# dub_synth.net
KiCad netlist of a schematic drawn in Altium Designer
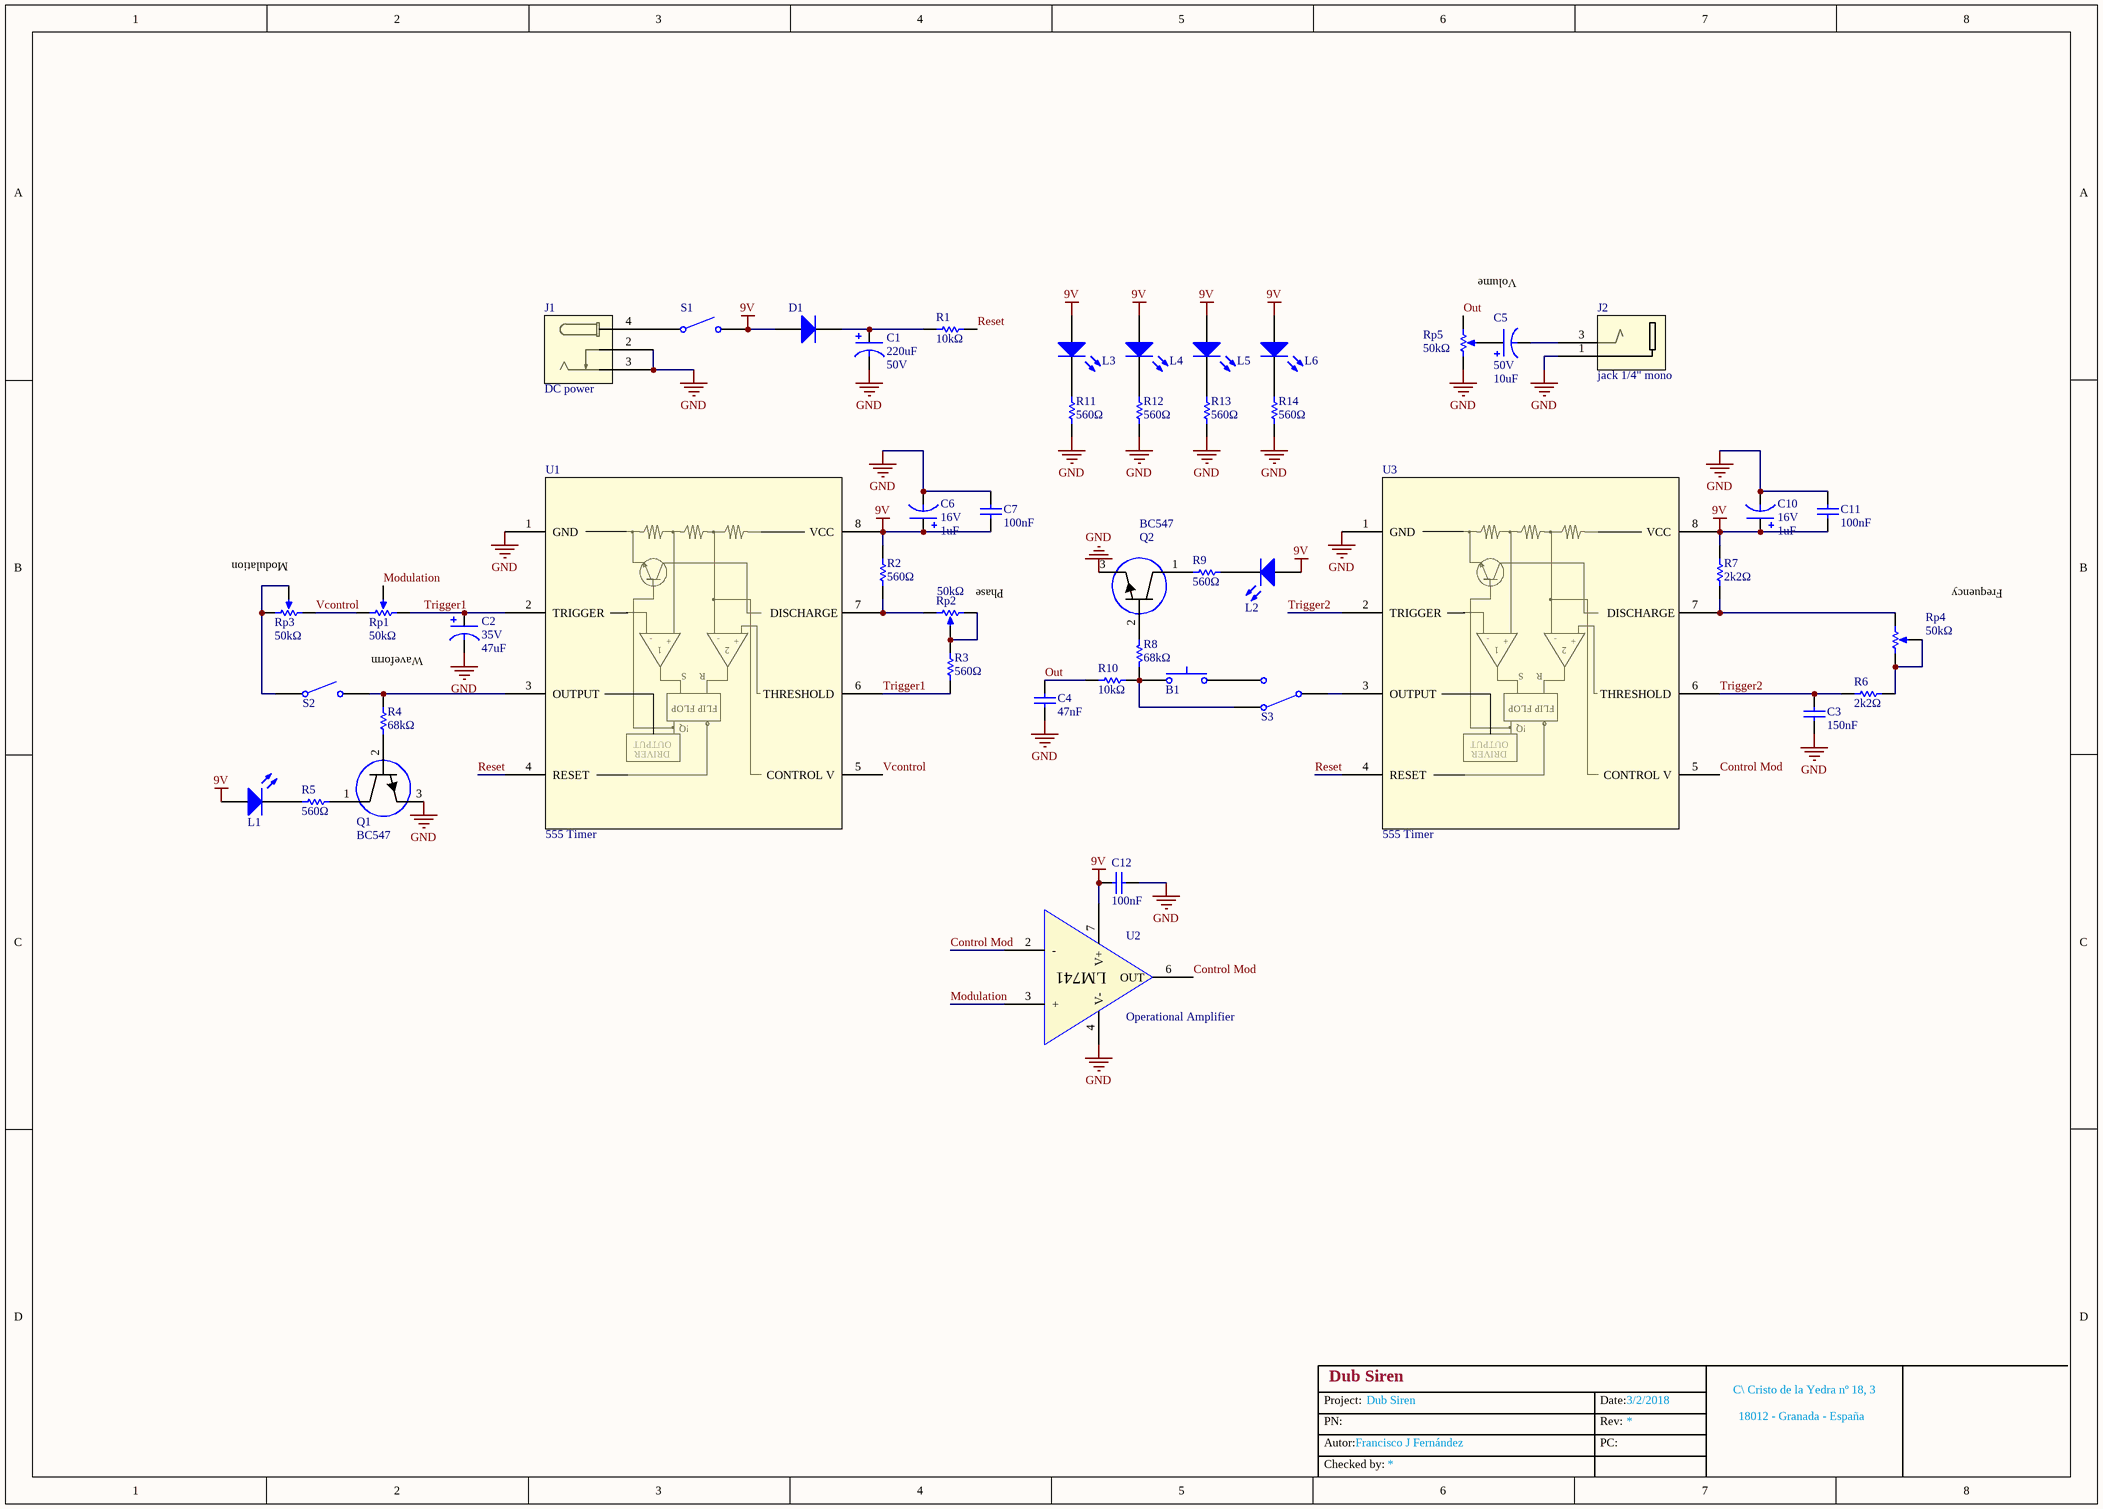
[diagram p0: dub synth.SchDoc]

(export (version "E")
  (design (tool "Eeschema 10.0.6"))
  (components
    (comp (ref "B1")
      (value "SPST Momentary")
      (footprint "SPSTM")
      (description "Push-to-make, SPST Momentary")
      (libsource (lib "componentes") (part "SPSTM"))
    )
    (comp (ref "C1")
      (value "Capacitor Electrolitic")
      (footprint "AXIAL 0.5 - CAP ELECT")
      (description "Aluminum Capacitor Electrolitic")
      (fields (field (name "CAPACITANCE") "220uF") (field (name "VOLTAGE RATING") "50V"))
      (libsource (lib "componentes") (part "Capacitor Electrolitic"))
    )
    (comp (ref "C2")
      (value "Capacitor Electrolitic")
      (footprint "Axial 0.26 - Cap Elect")
      (description "Aluminum Capacitor Electrolitic")
      (fields (field (name "VOLTAGE RATING") "35V") (field (name "CAPACITANCE") "47uF"))
      (libsource (lib "componentes") (part "Capacitor Electrolitic"))
    )
    (comp (ref "C3")
      (value "150nF")
      (footprint "Axial 5 - Cap Ceramic")
      (description "Capacitor")
      (fields (field (name "PUBLISHER") "Altium Limited"))
      (libsource (lib "componentes") (part "Capacitor"))
    )
    (comp (ref "C4")
      (value "47nF")
      (footprint "Axial 5 - Cap Lentil")
      (description "Capacitor")
      (fields (field (name "PUBLISHER") "Altium Limited"))
      (libsource (lib "componentes") (part "Capacitor"))
    )
    (comp (ref "C5")
      (value "Capacitor Electrolitic")
      (footprint "Axial 0.26 - Cap Elect")
      (description "Aluminum Capacitor Electrolitic")
      (fields (field (name "VOLTAGE RATING") "50V") (field (name "CAPACITANCE") "10uF"))
      (libsource (lib "") (part "Capacitor Electrolitic_1"))
    )
    (comp (ref "C6")
      (value "Capacitor Electrolitic")
      (footprint "Axial 0.26 - Cap Elect")
      (description "Aluminum Capacitor Electrolitic")
      (fields (field (name "VOLTAGE RATING") "16V") (field (name "CAPACITANCE") "1uF"))
      (libsource (lib "componentes") (part "Capacitor Electrolitic"))
    )
    (comp (ref "C7")
      (value "100nF")
      (footprint "Axial 5 - Cap Lentil")
      (description "Capacitor")
      (fields (field (name "PUBLISHER") "Altium Limited"))
      (libsource (lib "componentes") (part "Capacitor"))
    )
    (comp (ref "C10")
      (value "Capacitor Electrolitic")
      (footprint "Axial 0.26 - Cap Elect")
      (description "Aluminum Capacitor Electrolitic")
      (fields (field (name "VOLTAGE RATING") "16V") (field (name "CAPACITANCE") "1uF"))
      (libsource (lib "componentes") (part "Capacitor Electrolitic"))
    )
    (comp (ref "C11")
      (value "100nF")
      (footprint "Axial 5 - Cap Lentil")
      (description "Capacitor")
      (fields (field (name "PUBLISHER") "Altium Limited"))
      (libsource (lib "componentes") (part "Capacitor"))
    )
    (comp (ref "C12")
      (value "100nF")
      (footprint "Axial 5 - Cap Lentil")
      (description "Capacitor")
      (fields (field (name "PUBLISHER") "Altium Limited"))
      (libsource (lib "componentes") (part "Capacitor"))
    )
    (comp (ref "D1")
      (value "Diode")
      (footprint "AXIAL - 0.76 DIODE")
      (description "1.0A rectifier")
      (libsource (lib "componentes") (part "1N4001"))
    )
    (comp (ref "J1")
      (value "DC power")
      (footprint "DC Power")
      (description "Jack DC 2.1mm, 3 contactos")
      (libsource (lib "conectores") (part "DC power"))
    )
    (comp (ref "J2")
      (value "jack 1/4\" mono")
      (footprint "jack 1/4\" mono")
      (description "Conectores de audio 1/4\"JACK MTL NUT INSERT W/GRIP PTS")
      (libsource (lib "conectores") (part "jack 1/4{dblquote} mono"))
    )
    (comp (ref "L1")
      (value "LED")
      (footprint "Axial 0.26 - LED")
      (description "General purpose LED")
      (libsource (lib "componentes") (part "LED"))
    )
    (comp (ref "L2")
      (value "LED")
      (footprint "Axial 0.26 - LED")
      (description "General purpose LED")
      (libsource (lib "componentes") (part "LED"))
    )
    (comp (ref "L3")
      (value "LED")
      (footprint "Axial 0.26 - LED")
      (description "General purpose LED")
      (libsource (lib "componentes") (part "LED"))
    )
    (comp (ref "L4")
      (value "LED")
      (footprint "Axial 0.26 - LED")
      (description "General purpose LED")
      (libsource (lib "componentes") (part "LED"))
    )
    (comp (ref "L5")
      (value "LED")
      (footprint "Axial 0.26 - LED")
      (description "General purpose LED")
      (libsource (lib "componentes") (part "LED"))
    )
    (comp (ref "L6")
      (value "LED")
      (footprint "Axial 0.26 - LED")
      (description "General purpose LED")
      (libsource (lib "componentes") (part "LED"))
    )
    (comp (ref "Q1")
      (value "BC547")
      (footprint "TO-92B")
      (description "Standart transistor")
      (libsource (lib "componentes") (part "Transistor"))
    )
    (comp (ref "Q2")
      (value "BC547")
      (footprint "TO-92B")
      (description "Standart transistor")
      (libsource (lib "componentes") (part "Transistor"))
    )
    (comp (ref "R1")
      (value "Resistor")
      (footprint "Axial - 1.0")
      (fields (field (name "RESISTANCE") "10kΩ"))
      (libsource (lib "componentes") (part "Resistor"))
    )
    (comp (ref "R2")
      (value "Resistor")
      (footprint "Axial - 1.0")
      (fields (field (name "RESISTANCE") "560Ω"))
      (libsource (lib "componentes") (part "Resistor"))
    )
    (comp (ref "R3")
      (value "Resistor")
      (footprint "Axial - 1.0")
      (fields (field (name "RESISTANCE") "560Ω"))
      (libsource (lib "componentes") (part "Resistor"))
    )
    (comp (ref "R4")
      (value "Resistor")
      (footprint "Axial - 1.0")
      (fields (field (name "RESISTANCE") "68kΩ"))
      (libsource (lib "componentes") (part "Resistor"))
    )
    (comp (ref "R5")
      (value "Resistor")
      (footprint "Axial - 1.0")
      (fields (field (name "RESISTANCE") "560Ω"))
      (libsource (lib "componentes") (part "Resistor"))
    )
    (comp (ref "R6")
      (value "Resistor")
      (footprint "Axial - 1.0")
      (fields (field (name "RESISTANCE") "2k2Ω"))
      (libsource (lib "componentes") (part "Resistor"))
    )
    (comp (ref "R7")
      (value "Resistor")
      (footprint "Axial - 1.0")
      (fields (field (name "RESISTANCE") "2k2Ω"))
      (libsource (lib "componentes") (part "Resistor"))
    )
    (comp (ref "R8")
      (value "Resistor")
      (footprint "Axial - 1.0")
      (fields (field (name "RESISTANCE") "68kΩ"))
      (libsource (lib "componentes") (part "Resistor"))
    )
    (comp (ref "R9")
      (value "Resistor")
      (footprint "Axial - 1.0")
      (fields (field (name "RESISTANCE") "560Ω"))
      (libsource (lib "componentes") (part "Resistor"))
    )
    (comp (ref "R10")
      (value "Resistor")
      (footprint "Axial - 1.0")
      (fields (field (name "RESISTANCE") "10kΩ"))
      (libsource (lib "componentes") (part "Resistor"))
    )
    (comp (ref "R11")
      (value "Resistor")
      (footprint "Axial - 1.0")
      (fields (field (name "RESISTANCE") "560Ω"))
      (libsource (lib "componentes") (part "Resistor"))
    )
    (comp (ref "R12")
      (value "Resistor")
      (footprint "Axial - 1.0")
      (fields (field (name "RESISTANCE") "560Ω"))
      (libsource (lib "componentes") (part "Resistor"))
    )
    (comp (ref "R13")
      (value "Resistor")
      (footprint "Axial - 1.0")
      (fields (field (name "RESISTANCE") "560Ω"))
      (libsource (lib "componentes") (part "Resistor"))
    )
    (comp (ref "R14")
      (value "Resistor")
      (footprint "Axial - 1.0")
      (fields (field (name "RESISTANCE") "560Ω"))
      (libsource (lib "componentes") (part "Resistor"))
    )
    (comp (ref "Rp1")
      (value "RPot")
      (footprint "R0904N Thonk")
      (description "Potentiometer")
      (fields (field (name "RESISTANCE") "50kΩ") (field (name "PUBLISHER") "Altium Limited"))
      (libsource (lib "componentes") (part "RPot"))
    )
    (comp (ref "Rp2")
      (value "RPot")
      (footprint "R0904N Thonk")
      (description "Potentiometer")
      (fields (field (name "RESISTANCE") "50kΩ") (field (name "PUBLISHER") "Altium Limited"))
      (libsource (lib "componentes") (part "RPot"))
    )
    (comp (ref "Rp3")
      (value "RPot")
      (footprint "R0904N Thonk")
      (description "Potentiometer")
      (fields (field (name "RESISTANCE") "50kΩ") (field (name "PUBLISHER") "Altium Limited"))
      (libsource (lib "componentes") (part "RPot"))
    )
    (comp (ref "Rp4")
      (value "RPot")
      (footprint "R0904N Thonk")
      (description "Potentiometer")
      (fields (field (name "RESISTANCE") "50kΩ") (field (name "PUBLISHER") "Altium Limited"))
      (libsource (lib "componentes") (part "RPot"))
    )
    (comp (ref "Rp5")
      (value "RPot")
      (footprint "R0904N Thonk")
      (description "Potentiometer")
      (fields (field (name "RESISTANCE") "50kΩ") (field (name "PUBLISHER") "Altium Limited"))
      (libsource (lib "componentes") (part "RPot"))
    )
    (comp (ref "S1")
      (value "SPST switch")
      (footprint "SPST")
      (description "Single Pole, Single Throw")
      (libsource (lib "componentes") (part "SPST"))
    )
    (comp (ref "S2")
      (value "SPST switch")
      (footprint "SPST")
      (description "Single Pole, Single Throw")
      (libsource (lib "componentes") (part "SPST"))
    )
    (comp (ref "S3")
      (value "SPDT Switch")
      (footprint "SPDT")
      (description "Single Pole, Double Throw")
      (libsource (lib "componentes") (part "SPDT"))
    )
    (comp (ref "U1")
      (value "555 Timer")
      (footprint "8 pins IC socket")
      (description "Accurate time delays or oscillation generator")
      (libsource (lib "integrados") (part "555"))
    )
    (comp (ref "U2")
      (value "Operational Amplifier")
      (footprint "8 pins IC socket")
      (description "General purpose operational amplifier")
      (libsource (lib "integrados") (part "LM741"))
    )
    (comp (ref "U3")
      (value "555 Timer")
      (footprint "8 pins IC socket")
      (description "Accurate time delays or oscillation generator")
      (libsource (lib "integrados") (part "555"))
    )
  )
  (nets
    (net (code "1") (name "/Control Mod") (class "Default")
      (node (ref "U2") (pin "2") (pinfunction "-_2") (pintype "passive"))
      (node (ref "U2") (pin "6") (pinfunction "OUT_6") (pintype "passive"))
      (node (ref "U3") (pin "5") (pinfunction "CONTROL_V_5") (pintype "passive"))
    )
    (net (code "2") (name "/Modulation") (class "Default")
      (node (ref "Rp1") (pin "2") (pinfunction "TAP_2") (pintype "passive"))
      (node (ref "U2") (pin "3") (pinfunction "+_3") (pintype "passive"))
    )
    (net (code "3") (name "/Out") (class "Default")
      (node (ref "C4") (pin "2") (pinfunction "2_2") (pintype "passive"))
      (node (ref "R10") (pin "1") (pinfunction "1_1") (pintype "passive"))
      (node (ref "Rp5") (pin "3") (pinfunction "BOT_3") (pintype "passive"))
    )
    (net (code "4") (name "/Reset") (class "Default")
      (node (ref "R1") (pin "2") (pinfunction "2_2") (pintype "passive"))
      (node (ref "U1") (pin "4") (pinfunction "RESET_4") (pintype "passive"))
      (node (ref "U3") (pin "4") (pinfunction "RESET_4") (pintype "passive"))
    )
    (net (code "5") (name "/Trigger1") (class "Default")
      (node (ref "C2") (pin "2") (pintype "power_in"))
      (node (ref "R3") (pin "1") (pinfunction "1_1") (pintype "passive"))
      (node (ref "Rp1") (pin "1") (pinfunction "TOP_1") (pintype "passive"))
      (node (ref "U1") (pin "2") (pinfunction "TRIGGER_2") (pintype "passive"))
      (node (ref "U1") (pin "6") (pinfunction "THRESHOLD_6") (pintype "passive"))
    )
    (net (code "6") (name "/Trigger2") (class "Default")
      (node (ref "C3") (pin "2") (pinfunction "2_2") (pintype "passive"))
      (node (ref "R6") (pin "2") (pinfunction "2_2") (pintype "passive"))
      (node (ref "U3") (pin "2") (pinfunction "TRIGGER_2") (pintype "passive"))
      (node (ref "U3") (pin "6") (pinfunction "THRESHOLD_6") (pintype "passive"))
    )
    (net (code "7") (name "/Vcontrol") (class "Default")
      (node (ref "Rp1") (pin "3") (pinfunction "BOT_3") (pintype "passive"))
      (node (ref "Rp3") (pin "1") (pinfunction "TOP_1") (pintype "passive"))
      (node (ref "U1") (pin "5") (pinfunction "CONTROL_V_5") (pintype "passive"))
    )
    (net (code "8") (name "9V") (class "Default")
      (node (ref "C10") (pin "2") (pintype "power_in"))
      (node (ref "C11") (pin "2") (pinfunction "2_2") (pintype "passive"))
      (node (ref "C12") (pin "1") (pinfunction "1_1") (pintype "passive"))
      (node (ref "C6") (pin "2") (pintype "power_in"))
      (node (ref "C7") (pin "2") (pinfunction "2_2") (pintype "passive"))
      (node (ref "D1") (pin "1") (pinfunction "A_1") (pintype "passive"))
      (node (ref "L1") (pin "1") (pinfunction "A_1") (pintype "passive"))
      (node (ref "L2") (pin "1") (pinfunction "A_1") (pintype "passive"))
      (node (ref "L3") (pin "1") (pinfunction "A_1") (pintype "passive"))
      (node (ref "L4") (pin "1") (pinfunction "A_1") (pintype "passive"))
      (node (ref "L5") (pin "1") (pinfunction "A_1") (pintype "passive"))
      (node (ref "L6") (pin "1") (pinfunction "A_1") (pintype "passive"))
      (node (ref "R2") (pin "2") (pinfunction "2_2") (pintype "passive"))
      (node (ref "R7") (pin "2") (pinfunction "2_2") (pintype "passive"))
      (node (ref "S1") (pin "2") (pinfunction "2_2") (pintype "passive"))
      (node (ref "U1") (pin "8") (pinfunction "VCC_8") (pintype "passive"))
      (node (ref "U2") (pin "7") (pinfunction "V+_7") (pintype "passive"))
      (node (ref "U3") (pin "8") (pinfunction "VCC_8") (pintype "passive"))
    )
    (net (code "9") (name "GND") (class "Default")
      (node (ref "C1") (pin "1") (pintype "power_in"))
      (node (ref "C10") (pin "1") (pintype "power_in"))
      (node (ref "C11") (pin "1") (pinfunction "1_1") (pintype "passive"))
      (node (ref "C12") (pin "2") (pinfunction "2_2") (pintype "passive"))
      (node (ref "C2") (pin "1") (pintype "power_in"))
      (node (ref "C3") (pin "1") (pinfunction "1_1") (pintype "passive"))
      (node (ref "C4") (pin "1") (pinfunction "1_1") (pintype "passive"))
      (node (ref "C6") (pin "1") (pintype "power_in"))
      (node (ref "C7") (pin "1") (pinfunction "1_1") (pintype "passive"))
      (node (ref "J1") (pin "2") (pintype "passive"))
      (node (ref "J1") (pin "3") (pintype "passive"))
      (node (ref "J2") (pin "1") (pintype "passive"))
      (node (ref "Q1") (pin "3") (pinfunction "Emitter_3") (pintype "passive"))
      (node (ref "Q2") (pin "3") (pinfunction "Emitter_3") (pintype "passive"))
      (node (ref "R11") (pin "1") (pinfunction "1_1") (pintype "passive"))
      (node (ref "R12") (pin "1") (pinfunction "1_1") (pintype "passive"))
      (node (ref "R13") (pin "1") (pinfunction "1_1") (pintype "passive"))
      (node (ref "R14") (pin "1") (pinfunction "1_1") (pintype "passive"))
      (node (ref "Rp5") (pin "1") (pinfunction "TOP_1") (pintype "passive"))
      (node (ref "U1") (pin "1") (pinfunction "GND_1") (pintype "passive"))
      (node (ref "U3") (pin "1") (pinfunction "GND_1") (pintype "passive"))
    )
    (net (code "10") (name "Net-(B1-Pad1)") (class "Default")
      (node (ref "B1") (pin "1") (pinfunction "1_1") (pintype "passive"))
      (node (ref "R10") (pin "2") (pinfunction "2_2") (pintype "passive"))
      (node (ref "R8") (pin "1") (pinfunction "1_1") (pintype "passive"))
      (node (ref "S3") (pin "2") (pinfunction "2_2") (pintype "passive"))
    )
    (net (code "11") (name "Net-(B1-Pad2)") (class "Default")
      (node (ref "B1") (pin "2") (pinfunction "2_2") (pintype "passive"))
      (node (ref "S3") (pin "3") (pinfunction "3_3") (pintype "passive"))
    )
    (net (code "12") (name "Net-(C5-Pad1)") (class "Default")
      (node (ref "C5") (pin "1") (pintype "power_in"))
      (node (ref "J2") (pin "3") (pintype "passive"))
    )
    (net (code "13") (name "Net-(D1-K)") (class "Default")
      (node (ref "C1") (pin "2") (pintype "power_in"))
      (node (ref "D1") (pin "2") (pinfunction "K_2") (pintype "passive"))
      (node (ref "R1") (pin "1") (pinfunction "1_1") (pintype "passive"))
    )
    (net (code "14") (name "Net-(J1-Pad4)") (class "Default")
      (node (ref "J1") (pin "4") (pintype "passive"))
      (node (ref "S1") (pin "1") (pinfunction "1_1") (pintype "passive"))
    )
    (net (code "15") (name "Net-(L1-K)") (class "Default")
      (node (ref "L1") (pin "2") (pinfunction "K_2") (pintype "passive"))
      (node (ref "R5") (pin "1") (pinfunction "1_1") (pintype "passive"))
    )
    (net (code "16") (name "Net-(L2-K)") (class "Default")
      (node (ref "L2") (pin "2") (pinfunction "K_2") (pintype "passive"))
      (node (ref "R9") (pin "1") (pinfunction "1_1") (pintype "passive"))
    )
    (net (code "17") (name "Net-(L3-K)") (class "Default")
      (node (ref "L3") (pin "2") (pinfunction "K_2") (pintype "passive"))
      (node (ref "R11") (pin "2") (pinfunction "2_2") (pintype "passive"))
    )
    (net (code "18") (name "Net-(L4-K)") (class "Default")
      (node (ref "L4") (pin "2") (pinfunction "K_2") (pintype "passive"))
      (node (ref "R12") (pin "2") (pinfunction "2_2") (pintype "passive"))
    )
    (net (code "19") (name "Net-(L5-K)") (class "Default")
      (node (ref "L5") (pin "2") (pinfunction "K_2") (pintype "passive"))
      (node (ref "R13") (pin "2") (pinfunction "2_2") (pintype "passive"))
    )
    (net (code "20") (name "Net-(L6-K)") (class "Default")
      (node (ref "L6") (pin "2") (pinfunction "K_2") (pintype "passive"))
      (node (ref "R14") (pin "2") (pinfunction "2_2") (pintype "passive"))
    )
    (net (code "21") (name "Net-(Q1-Base)") (class "Default")
      (node (ref "Q1") (pin "2") (pinfunction "Base_2") (pintype "passive"))
      (node (ref "R4") (pin "1") (pinfunction "1_1") (pintype "passive"))
    )
    (net (code "22") (name "Net-(Q1-Collector)") (class "Default")
      (node (ref "Q1") (pin "1") (pinfunction "Collector_1") (pintype "passive"))
      (node (ref "R5") (pin "2") (pinfunction "2_2") (pintype "passive"))
    )
    (net (code "23") (name "Net-(Q2-Base)") (class "Default")
      (node (ref "Q2") (pin "2") (pinfunction "Base_2") (pintype "passive"))
      (node (ref "R8") (pin "2") (pinfunction "2_2") (pintype "passive"))
    )
    (net (code "24") (name "Net-(Q2-Collector)") (class "Default")
      (node (ref "Q2") (pin "1") (pinfunction "Collector_1") (pintype "passive"))
      (node (ref "R9") (pin "2") (pinfunction "2_2") (pintype "passive"))
    )
    (net (code "25") (name "Net-(Rp2-BOT)") (class "Default")
      (node (ref "R3") (pin "2") (pinfunction "2_2") (pintype "passive"))
      (node (ref "Rp2") (pin "2") (pinfunction "TAP_2") (pintype "passive"))
      (node (ref "Rp2") (pin "3") (pinfunction "BOT_3") (pintype "passive"))
    )
    (net (code "26") (name "Net-(Rp2-TOP)") (class "Default")
      (node (ref "R2") (pin "1") (pinfunction "1_1") (pintype "passive"))
      (node (ref "Rp2") (pin "1") (pinfunction "TOP_1") (pintype "passive"))
      (node (ref "U1") (pin "7") (pinfunction "DISCHARGE_7") (pintype "passive"))
    )
    (net (code "27") (name "Net-(Rp3-BOT)") (class "Default")
      (node (ref "Rp3") (pin "2") (pinfunction "TAP_2") (pintype "passive"))
      (node (ref "Rp3") (pin "3") (pinfunction "BOT_3") (pintype "passive"))
      (node (ref "S2") (pin "1") (pinfunction "1_1") (pintype "passive"))
    )
    (net (code "28") (name "Net-(Rp4-BOT)") (class "Default")
      (node (ref "R7") (pin "1") (pinfunction "1_1") (pintype "passive"))
      (node (ref "Rp4") (pin "3") (pinfunction "BOT_3") (pintype "passive"))
      (node (ref "U3") (pin "7") (pinfunction "DISCHARGE_7") (pintype "passive"))
    )
    (net (code "29") (name "Net-(Rp4-TAP)") (class "Default")
      (node (ref "R6") (pin "1") (pinfunction "1_1") (pintype "passive"))
      (node (ref "Rp4") (pin "1") (pinfunction "TOP_1") (pintype "passive"))
      (node (ref "Rp4") (pin "2") (pinfunction "TAP_2") (pintype "passive"))
    )
    (net (code "30") (name "Net-(Rp5-TAP)") (class "Default")
      (node (ref "C5") (pin "2") (pintype "power_in"))
      (node (ref "Rp5") (pin "2") (pinfunction "TAP_2") (pintype "passive"))
    )
    (net (code "31") (name "Net-(U1-OUTPUT)") (class "Default")
      (node (ref "R4") (pin "2") (pinfunction "2_2") (pintype "passive"))
      (node (ref "S2") (pin "2") (pinfunction "2_2") (pintype "passive"))
      (node (ref "U1") (pin "3") (pinfunction "OUTPUT_3") (pintype "passive"))
    )
    (net (code "32") (name "Net-(U3-OUTPUT)") (class "Default")
      (node (ref "S3") (pin "1") (pinfunction "1_1") (pintype "passive"))
      (node (ref "U3") (pin "3") (pinfunction "OUTPUT_3") (pintype "passive"))
    )
    (net (code "33") (name "unconnected-(U2-V--Pad4)") (class "Default")
      (node (ref "U2") (pin "4") (pinfunction "V-_4") (pintype "passive"))
    )
  )
)
